# Probe.net
KiCad netlist of a schematic drawn in Altium Designer
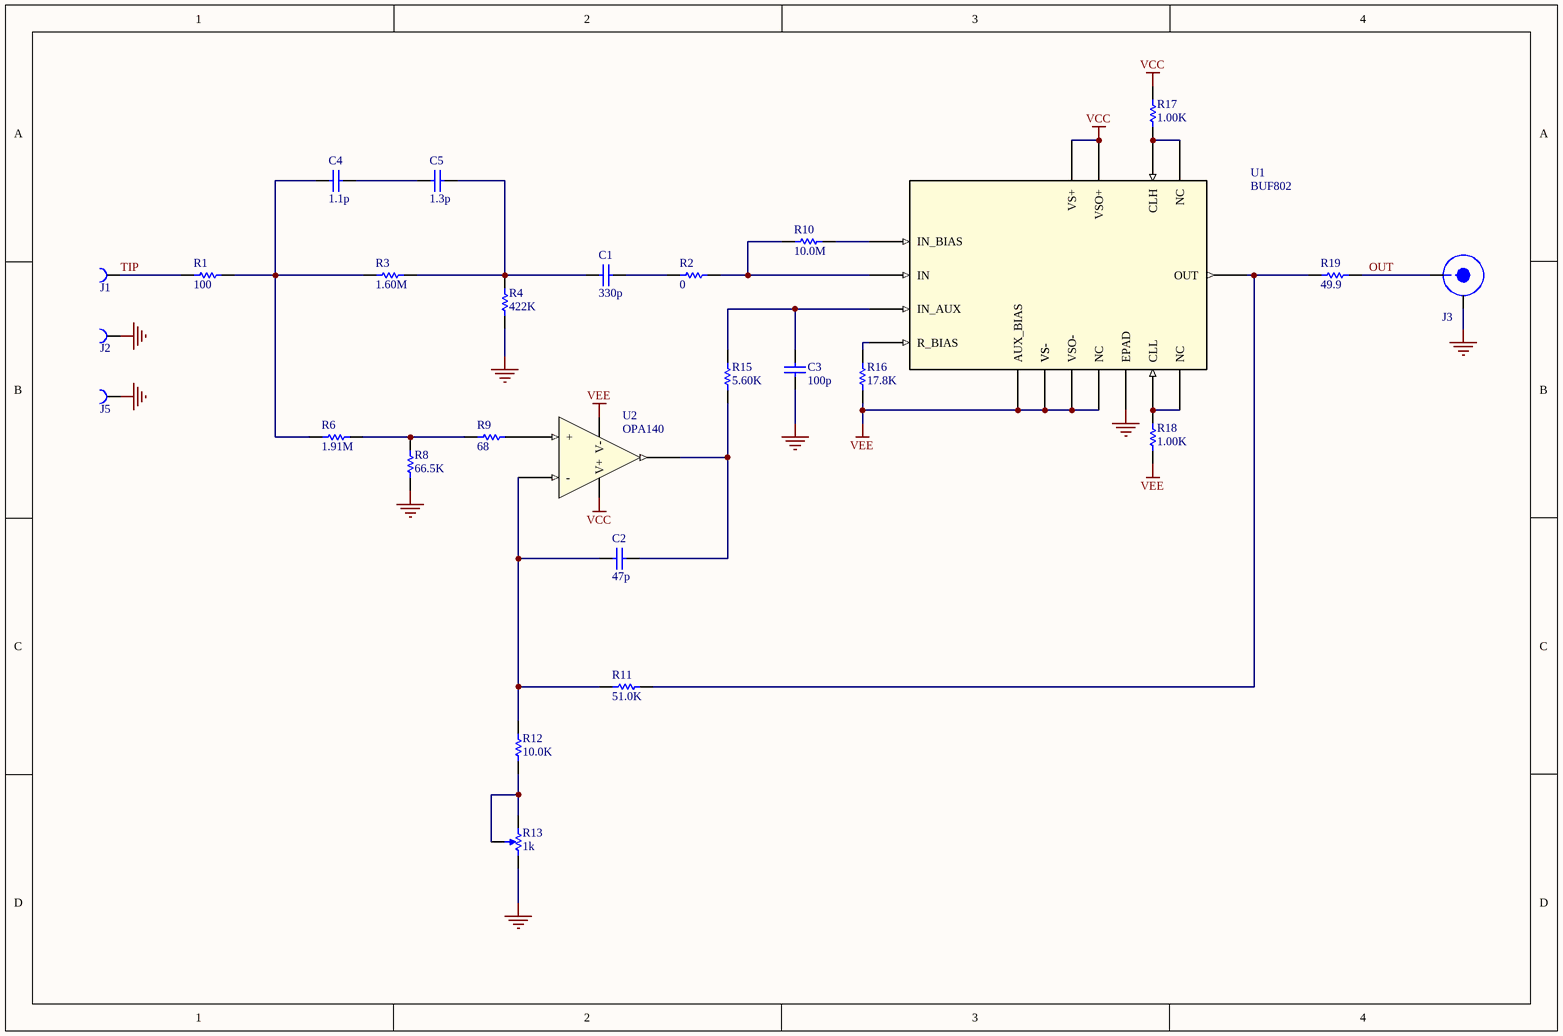
[diagram p0: Probe.SchDoc]

(export (version "E")
  (design (tool "Eeschema 10.0.6"))
  (components
    (comp (ref "C1")
      (value "330p")
      (footprint "CAPC0402(1005)50_M")
      (description "CAP CER 330PF±5% 50V C0G 0402")
      (fields
        (field (name "MANUFACTURER") "Murata")
        (field (name "MANUFACTURER PART NUMBER") "GRM1555C1H331JA01D")
      )
      (libsource (lib "Murata GRM 0402") (part "Capacitor_Generic"))
    )
    (comp (ref "C2")
      (value "47p")
      (footprint "CAPC0402(1005)50_M")
      (description "CAP CER 47PF±5% 50V C0G 0402")
      (fields
        (field (name "MANUFACTURER") "Samsung Electro-Mechanics")
        (field (name "MANUFACTURER PART NUMBER") "CL05C470JB5NNNC")
      )
      (libsource (lib "Samsung CAPC0402") (part "Capacitor_Generic"))
    )
    (comp (ref "C3")
      (value "100p")
      (footprint "CAPC0402(1005)50_M")
      (description "CAP CER 100PF±5% 50V C0G 0402")
      (fields
        (field (name "MANUFACTURER") "Samsung Electro-Mechanics")
        (field (name "MANUFACTURER PART NUMBER") "CL05C101JB5NNNC")
      )
      (libsource (lib "Samsung CAPC0402") (part "Capacitor_Generic"))
    )
    (comp (ref "C4")
      (value "1.1p")
      (footprint "CAPC0402(1005)50_M")
      (description "CAP CER 1.1PF±0.05PF 50V C0G/NP0 0402")
      (fields (field (name "PART NUMBER") "GJM1555C1H1R1WB01") (field (name "TOLERANCE") "±0.05pF"))
      (libsource (lib "Murata GJM 0402") (part "Capacitor_Generic"))
    )
    (comp (ref "C5")
      (value "1.3p")
      (footprint "CAPC0402(1005)50_M")
      (description "CAP CER 1.3PF±0.05PF 50V C0G/NP0 0402")
      (fields (field (name "PART NUMBER") "GJM1555C1H1R3WB01") (field (name "TOLERANCE") "±0.05pF"))
      (libsource (lib "Murata GJM 0402") (part "Capacitor_Generic"))
    )
    (comp (ref "J1")
      (value "0339-0-15-01-15-27-10-0")
      (footprint "MILL-MAX 0339")
      (description "CONN PIN RCPT")
      (fields (field (name "MANUFACTURER") "Mill-Max"))
      (libsource (lib "Connectors") (part "0339-0-15-01-15-27-10-0"))
    )
    (comp (ref "J2")
      (value "0339-0-15-01-15-27-10-0")
      (footprint "MILL-MAX 0339")
      (description "CONN PIN RCPT")
      (fields (field (name "MANUFACTURER") "Mill-Max"))
      (libsource (lib "Connectors") (part "0339-0-15-01-15-27-10-0"))
    )
    (comp (ref "J3")
      (value "901-10511-3")
      (footprint "901-10511-3")
      (description "CONN SMA JACK STR 50OHM EDGE MNT")
      (fields (field (name "MANUFACTURER") "Amphenol RF"))
      (libsource (lib "Connectors") (part "901-10511-3"))
    )
    (comp (ref "J5")
      (value "0339-0-15-01-15-27-10-0")
      (footprint "MILL-MAX 0339")
      (description "CONN PIN RCPT")
      (fields (field (name "MANUFACTURER") "Mill-Max"))
      (libsource (lib "Connectors") (part "0339-0-15-01-15-27-10-0"))
    )
    (comp (ref "R1")
      (value "100")
      (footprint "RESC0402(1005)_M")
      (description "RES 100 OHM 1% 1/16W 0402")
      (fields (field (name "PART NUMBER") "RESC0402-100R-1pct"))
      (libsource (lib "R0402 - 1pct") (part "Resistor_Generic"))
    )
    (comp (ref "R2")
      (value "0")
      (footprint "RESC0402(1005)_M")
      (description "RES 0 OHM JUMPER 0402")
      (fields (field (name "PART NUMBER") "R0402-0R0-JMP"))
      (libsource (lib "R0402 - 1pct") (part "Resistor_Generic"))
    )
    (comp (ref "R3")
      (value "1.60M")
      (footprint "RESC0402(1005)_M")
      (description "RES 1.60M OHM 1% 1/16W 0402")
      (fields (field (name "PART NUMBER") "RESC0402-1M60-1pct"))
      (libsource (lib "R0402 - 1pct") (part "Resistor_Generic"))
    )
    (comp (ref "R4")
      (value "422K")
      (footprint "RESC0402(1005)_M")
      (description "RES 422K OHM 1% 1/16W 0402")
      (fields (field (name "PART NUMBER") "RESC0402-422K-1pct"))
      (libsource (lib "R0402 - 1pct") (part "Resistor_Generic"))
    )
    (comp (ref "R6")
      (value "1.91M")
      (footprint "RESC0402(1005)_M")
      (description "RES 1.91M OHM 1% 1/16W 0402")
      (fields (field (name "PART NUMBER") "RESC0402-1M91-1pct"))
      (libsource (lib "R0402 - 1pct") (part "Resistor_Generic"))
    )
    (comp (ref "R8")
      (value "66.5K")
      (footprint "RESC0402(1005)_M")
      (description "RES 66.5K OHM 1% 1/16W 0402")
      (fields (field (name "PART NUMBER") "RESC0402-66K5-1pct"))
      (libsource (lib "R0402 - 1pct") (part "Resistor_Generic"))
    )
    (comp (ref "R9")
      (value "68")
      (footprint "RESC0402(1005)_M")
      (description "RES 68 OHM 1% 1/16W 0402")
      (fields (field (name "PART NUMBER") "RESC0402-68R0-1pct"))
      (libsource (lib "R0402 - 1pct") (part "Resistor_Generic"))
    )
    (comp (ref "R10")
      (value "10.0M")
      (footprint "RESC0402(1005)_M")
      (description "RES 10.0M OHM 1% 1/16W 0402")
      (fields (field (name "PART NUMBER") "RESC0402-10M0-1pct"))
      (libsource (lib "R0402 - 1pct") (part "Resistor_Generic"))
    )
    (comp (ref "R11")
      (value "51.0K")
      (footprint "RESC0402(1005)_M")
      (description "RES 51.0K OHM 1% 1/16W 0402")
      (fields (field (name "PART NUMBER") "RESC0402-51K0-1pct"))
      (libsource (lib "R0402 - 1pct") (part "Resistor_Generic"))
    )
    (comp (ref "R12")
      (value "10.0K")
      (footprint "RESC0402(1005)_M")
      (description "RES 10.0K OHM 1% 1/16W 0402")
      (fields (field (name "PART NUMBER") "RESC0402-10K0-1pct"))
      (libsource (lib "R0402 - 1pct") (part "Resistor_Generic"))
    )
    (comp (ref "R13")
      (value "1k")
      (footprint "PVG3A")
      (description "TRIMMER 1K OHM 0.25W J LEAD TOP")
      (fields
        (field (name "MANUFACTURER") "Bourns")
        (field (name "MANUFACTURER PART NUMBER") "PVG3A102C01R00")
      )
      (libsource (lib "Trimpots") (part "PVG3A102C01R00"))
    )
    (comp (ref "R15")
      (value "5.60K")
      (footprint "RESC0402(1005)_M")
      (description "RES 5.60K OHM 1% 1/16W 0402")
      (fields (field (name "PART NUMBER") "RESC0402-5K60-1pct"))
      (libsource (lib "R0402 - 1pct") (part "Resistor_Generic"))
    )
    (comp (ref "R16")
      (value "17.8K")
      (footprint "RESC0402(1005)_M")
      (description "RES 17.8K OHM 1% 1/16W 0402")
      (fields (field (name "PART NUMBER") "RESC0402-17K8-1pct"))
      (libsource (lib "R0402 - 1pct") (part "Resistor_Generic"))
    )
    (comp (ref "R17")
      (value "1.00K")
      (footprint "RESC0402(1005)_M")
      (description "RES 1.00K OHM 1% 1/16W 0402")
      (fields (field (name "PART NUMBER") "RESC0402-1K00-1pct"))
      (libsource (lib "R0402 - 1pct") (part "Resistor_Generic"))
    )
    (comp (ref "R18")
      (value "1.00K")
      (footprint "RESC0402(1005)_M")
      (description "RES 1.00K OHM 1% 1/16W 0402")
      (fields (field (name "PART NUMBER") "RESC0402-1K00-1pct"))
      (libsource (lib "R0402 - 1pct") (part "Resistor_Generic"))
    )
    (comp (ref "R19")
      (value "49.9")
      (footprint "RESC0402(1005)_M")
      (description "RES 49.9 OHM 1% 1/16W 0402")
      (fields (field (name "PART NUMBER") "RESC0402-49R9-1pct"))
      (libsource (lib "R0402 - 1pct") (part "Resistor_Generic"))
    )
    (comp (ref "U1")
      (value "BUF802")
      (footprint "VQFN16_RGT_TEX- OSHPARK")
      (description "WIDE-BANDWIDTH JFET BUFFER")
      (fields
        (field (name "MANUFACTURER") "Texas Instruments")
        (field (name "MANUFACTURER PART NUMBER") "BUF802IRGTR")
      )
      (libsource (lib "IC") (part "BUF802IRGTR"))
    )
    (comp (ref "U2")
      (value "OPA140")
      (footprint "SOIC-8")
      (description "IC OPAMP JFET 1 CIRCUIT 8SOIC")
      (fields
        (field (name "MANUFACTURER") "Texas Instruments")
        (field (name "MANUFACTURER PART NUMBER") "OPA140AIDR")
      )
      (libsource (lib "IC") (part "OPA140AIDR"))
    )
  )
  (nets
    (net (code "1") (name "/OUT") (class "Default")
      (node (ref "J3") (pin "1") (pinfunction "1_1") (pintype "passive"))
      (node (ref "R19") (pin "2") (pinfunction "2_2") (pintype "passive"))
    )
    (net (code "2") (name "/TIP") (class "Default")
      (node (ref "J1") (pin "1") (pinfunction "1_1") (pintype "passive"))
      (node (ref "R1") (pin "1") (pinfunction "1_1") (pintype "passive"))
    )
    (net (code "3") (name "GND") (class "Default")
      (node (ref "C3") (pin "2") (pinfunction "2_2") (pintype "passive"))
      (node (ref "J2") (pin "1") (pinfunction "1_1") (pintype "passive"))
      (node (ref "J3") (pin "2") (pinfunction "2_2") (pintype "passive"))
      (node (ref "J5") (pin "1") (pinfunction "1_1") (pintype "passive"))
      (node (ref "R13") (pin "3") (pinfunction "3_3") (pintype "passive"))
      (node (ref "R4") (pin "2") (pinfunction "2_2") (pintype "passive"))
      (node (ref "R8") (pin "2") (pinfunction "2_2") (pintype "passive"))
      (node (ref "U1") (pin "17") (pinfunction "EPAD_17") (pintype "passive"))
    )
    (net (code "4") (name "Net-(C1-Pad1)") (class "Default")
      (node (ref "C1") (pin "1") (pinfunction "1_1") (pintype "passive"))
      (node (ref "C5") (pin "2") (pinfunction "2_2") (pintype "passive"))
      (node (ref "R3") (pin "2") (pinfunction "2_2") (pintype "passive"))
      (node (ref "R4") (pin "1") (pinfunction "1_1") (pintype "passive"))
    )
    (net (code "5") (name "Net-(C1-Pad2)") (class "Default")
      (node (ref "C1") (pin "2") (pinfunction "2_2") (pintype "passive"))
      (node (ref "R2") (pin "1") (pinfunction "1_1") (pintype "passive"))
    )
    (net (code "6") (name "Net-(C4-Pad1)") (class "Default")
      (node (ref "C4") (pin "1") (pinfunction "1_1") (pintype "passive"))
      (node (ref "R1") (pin "2") (pinfunction "2_2") (pintype "passive"))
      (node (ref "R3") (pin "1") (pinfunction "1_1") (pintype "passive"))
      (node (ref "R6") (pin "1") (pinfunction "1_1") (pintype "passive"))
    )
    (net (code "7") (name "Net-(C4-Pad2)") (class "Default")
      (node (ref "C4") (pin "2") (pinfunction "2_2") (pintype "passive"))
      (node (ref "C5") (pin "1") (pinfunction "1_1") (pintype "passive"))
    )
    (net (code "8") (name "Net-(R6-Pad2)") (class "Default")
      (node (ref "R6") (pin "2") (pinfunction "2_2") (pintype "passive"))
      (node (ref "R8") (pin "1") (pinfunction "1_1") (pintype "passive"))
      (node (ref "R9") (pin "1") (pinfunction "1_1") (pintype "passive"))
    )
    (net (code "9") (name "Net-(R12-Pad2)") (class "Default")
      (node (ref "R12") (pin "2") (pinfunction "2_2") (pintype "passive"))
      (node (ref "R13") (pin "1") (pinfunction "1_1") (pintype "passive"))
      (node (ref "R13") (pin "2") (pinfunction "2_2") (pintype "passive"))
    )
    (net (code "10") (name "Net-(U1-CLH)") (class "Default")
      (node (ref "R17") (pin "1") (pinfunction "1_1") (pintype "passive"))
      (node (ref "U1") (pin "15") (pinfunction "CLH_15") (pintype "input"))
      (node (ref "U1") (pin "16") (pinfunction "NC_16") (pintype "passive"))
    )
    (net (code "11") (name "Net-(U1-CLL)") (class "Default")
      (node (ref "R18") (pin "1") (pinfunction "1_1") (pintype "passive"))
      (node (ref "U1") (pin "13") (pinfunction "NC_13") (pintype "passive"))
      (node (ref "U1") (pin "14") (pinfunction "CLL_14") (pintype "input"))
    )
    (net (code "12") (name "Net-(U1-IN)") (class "Default")
      (node (ref "R10") (pin "1") (pinfunction "1_1") (pintype "passive"))
      (node (ref "R2") (pin "2") (pinfunction "2_2") (pintype "passive"))
      (node (ref "U1") (pin "2") (pinfunction "IN_2") (pintype "input"))
    )
    (net (code "13") (name "Net-(U1-IN_AUX)") (class "Default")
      (node (ref "C3") (pin "1") (pinfunction "1_1") (pintype "passive"))
      (node (ref "R15") (pin "1") (pinfunction "1_1") (pintype "passive"))
      (node (ref "U1") (pin "4") (pinfunction "IN_AUX_4") (pintype "input"))
    )
    (net (code "14") (name "Net-(U1-IN_BIAS)") (class "Default")
      (node (ref "R10") (pin "2") (pinfunction "2_2") (pintype "passive"))
      (node (ref "U1") (pin "3") (pinfunction "IN_BIAS_3") (pintype "input"))
    )
    (net (code "15") (name "Net-(U1-OUT)") (class "Default")
      (node (ref "R11") (pin "2") (pinfunction "2_2") (pintype "passive"))
      (node (ref "R19") (pin "1") (pinfunction "1_1") (pintype "passive"))
      (node (ref "U1") (pin "11") (pinfunction "OUT_11") (pintype "output"))
    )
    (net (code "16") (name "Net-(U1-R_BIAS)") (class "Default")
      (node (ref "R16") (pin "1") (pinfunction "1_1") (pintype "passive"))
      (node (ref "U1") (pin "7") (pinfunction "R_BIAS_7") (pintype "input"))
    )
    (net (code "17") (name "Net-(U2-+)") (class "Default")
      (node (ref "R9") (pin "2") (pinfunction "2_2") (pintype "passive"))
      (node (ref "U2") (pin "3") (pinfunction "+_3") (pintype "input"))
    )
    (net (code "18") (name "Net-(U2--)") (class "Default")
      (node (ref "C2") (pin "1") (pinfunction "1_1") (pintype "passive"))
      (node (ref "R11") (pin "1") (pinfunction "1_1") (pintype "passive"))
      (node (ref "R12") (pin "1") (pinfunction "1_1") (pintype "passive"))
      (node (ref "U2") (pin "2") (pinfunction "-_2") (pintype "input"))
    )
    (net (code "19") (name "Net-(U2-OUT)") (class "Default")
      (node (ref "C2") (pin "2") (pinfunction "2_2") (pintype "passive"))
      (node (ref "R15") (pin "2") (pinfunction "2_2") (pintype "passive"))
      (node (ref "U2") (pin "6") (pinfunction "OUT_6") (pintype "output"))
    )
    (net (code "20") (name "VCC") (class "Default")
      (node (ref "R17") (pin "2") (pinfunction "2_2") (pintype "passive"))
      (node (ref "U1") (pin "1") (pinfunction "VS+_1") (pintype "power_in"))
      (node (ref "U1") (pin "12") (pinfunction "VSO+_12") (pintype "power_in"))
      (node (ref "U2") (pin "7") (pinfunction "V+_7") (pintype "power_in"))
    )
    (net (code "21") (name "VEE") (class "Default")
      (node (ref "R16") (pin "2") (pinfunction "2_2") (pintype "passive"))
      (node (ref "R18") (pin "2") (pinfunction "2_2") (pintype "passive"))
      (node (ref "U1") (pin "10") (pinfunction "VSO-_10") (pintype "power_in"))
      (node (ref "U1") (pin "5") (pinfunction "VS-_5") (pintype "power_in"))
      (node (ref "U1") (pin "6") (pinfunction "AUX_BIAS_6") (pintype "power_in"))
      (node (ref "U1") (pin "8") (pinfunction "VS-_8") (pintype "power_in"))
      (node (ref "U1") (pin "9") (pinfunction "NC_9") (pintype "passive"))
      (node (ref "U2") (pin "4") (pinfunction "V-_4") (pintype "power_in"))
    )
  )
)
